# Power.net
KiCad netlist of a schematic drawn in Altium Designer
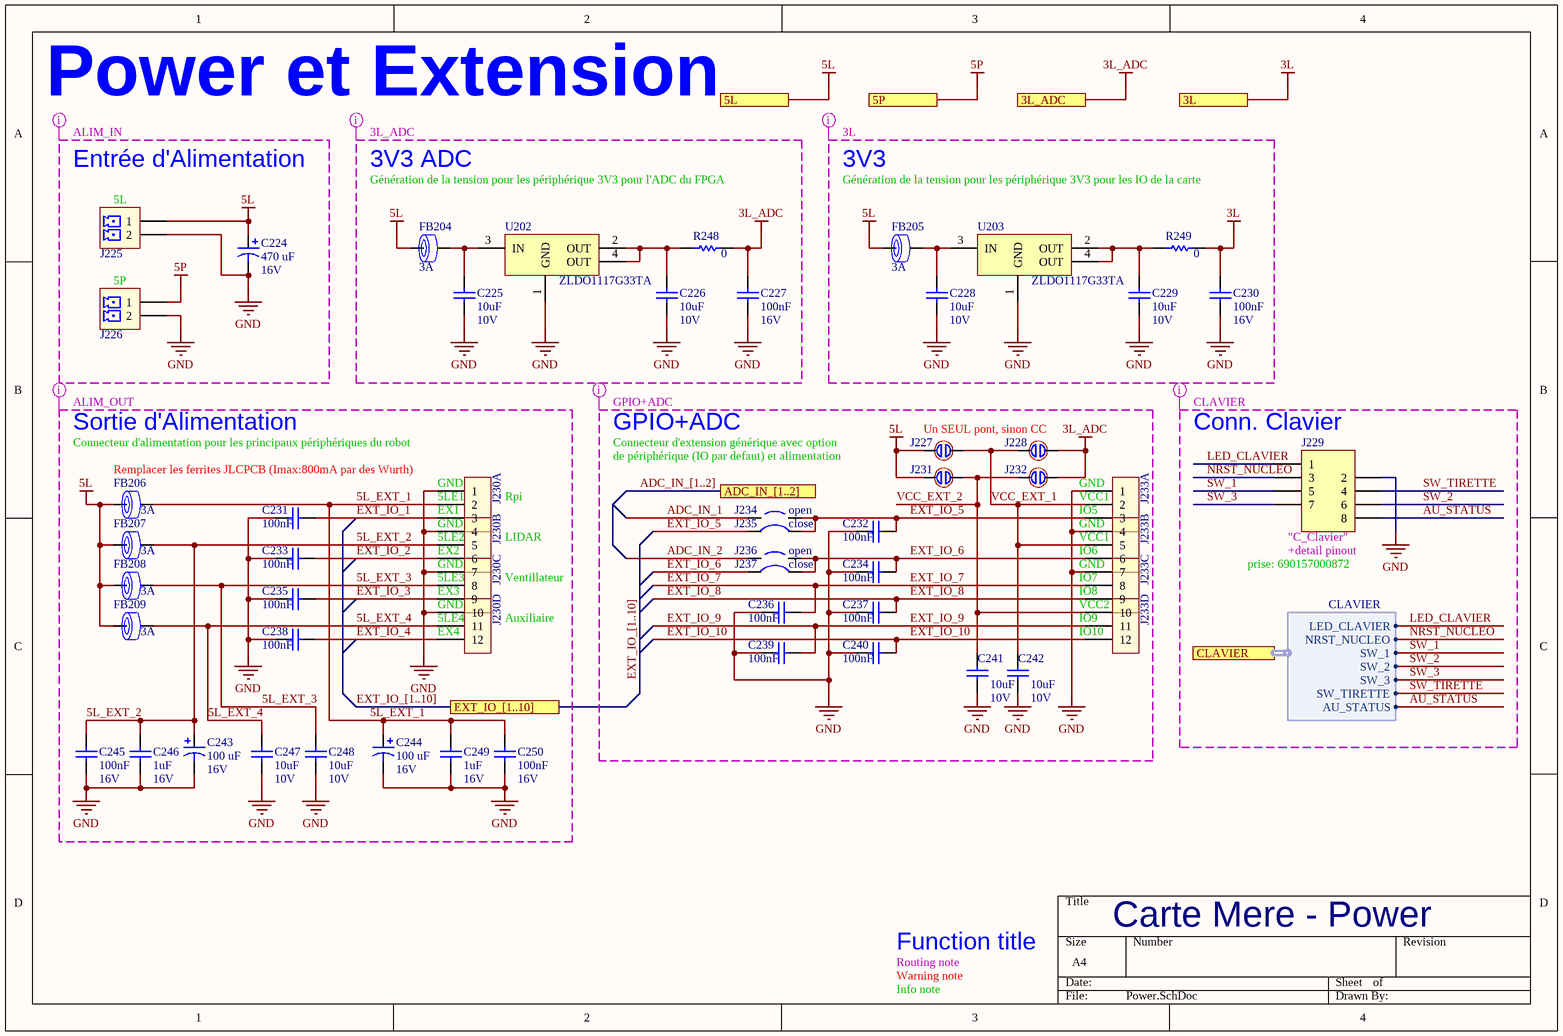
[diagram p0: Power.SchDoc]

(export (version "E")
  (design (tool "Eeschema 10.0.6"))
  (components
    (comp (ref "C224")
      (value "470 uF")
      (footprint "WCAP-ATG8_8x11.5x3.5x0.5")
      (description "CAP Alu 470 UF 20% 16 V")
      (fields
        (field (name "MANUFACTURER") "Wurth Elektronik")
        (field (name "MANUFACTURER PART NUMBER") "860010374012")
        (field (name "RATEDVOLTAGE") "16V")
      )
      (libsource (lib "Condensateur") (part "WCAP-ATG8, 860010374012"))
    )
    (comp (ref "C225")
      (value "10uF")
      (footprint "WCAP-CSGP_0805, 2x1.25x1.25")
      (description "CAP CER 10uF 10V X7R 0805")
      (fields
        (field (name "MANUFACTURER") "Wurth Elektronik")
        (field (name "MANUFACTURER PART NUMBER") "885012207026")
        (field (name "RATEDVOLTAGE") "10V")
      )
      (libsource (lib "Condensateur") (part "WCAP-CSGP, 885012207026"))
    )
    (comp (ref "C226")
      (value "10uF")
      (footprint "WCAP-CSGP_0805, 2x1.25x1.25")
      (description "CAP CER 10uF 10V X7R 0805")
      (fields
        (field (name "MANUFACTURER") "Wurth Elektronik")
        (field (name "MANUFACTURER PART NUMBER") "885012207026")
        (field (name "RATEDVOLTAGE") "10V")
      )
      (libsource (lib "Condensateur") (part "WCAP-CSGP, 885012207026"))
    )
    (comp (ref "C227")
      (value "100nF")
      (footprint "WCAP-CSGP_0402, 1x0.5x0.5")
      (description "CAP CER 100nF 16V X7R 0402")
      (fields
        (field (name "MANUFACTURER") "Wurth Elektronik")
        (field (name "MANUFACTURER PART NUMBER") "885012205037")
        (field (name "RATEDVOLTAGE") "16V")
      )
      (libsource (lib "Condensateur") (part "WCAP-CSGP, 885012205037"))
    )
    (comp (ref "C228")
      (value "10uF")
      (footprint "WCAP-CSGP_0805, 2x1.25x1.25")
      (description "CAP CER 10uF 10V X7R 0805")
      (fields
        (field (name "MANUFACTURER") "Wurth Elektronik")
        (field (name "MANUFACTURER PART NUMBER") "885012207026")
        (field (name "RATEDVOLTAGE") "10V")
      )
      (libsource (lib "Condensateur") (part "WCAP-CSGP, 885012207026"))
    )
    (comp (ref "C229")
      (value "10uF")
      (footprint "WCAP-CSGP_0805, 2x1.25x1.25")
      (description "CAP CER 10uF 10V X7R 0805")
      (fields
        (field (name "MANUFACTURER") "Wurth Elektronik")
        (field (name "MANUFACTURER PART NUMBER") "885012207026")
        (field (name "RATEDVOLTAGE") "10V")
      )
      (libsource (lib "Condensateur") (part "WCAP-CSGP, 885012207026"))
    )
    (comp (ref "C230")
      (value "100nF")
      (footprint "WCAP-CSGP_0402, 1x0.5x0.5")
      (description "CAP CER 100nF 16V X7R 0402")
      (fields
        (field (name "MANUFACTURER") "Wurth Elektronik")
        (field (name "MANUFACTURER PART NUMBER") "885012205037")
        (field (name "RATEDVOLTAGE") "16V")
      )
      (libsource (lib "Condensateur") (part "WCAP-CSGP, 885012205037"))
    )
    (comp (ref "C231")
      (value "100nF")
      (footprint "WCAP-CSGP_0402, 1x0.5x0.5")
      (description "CAP CER 100nF 16V X7R 0402")
      (fields
        (field (name "MANUFACTURER") "Wurth Elektronik")
        (field (name "MANUFACTURER PART NUMBER") "885012205037")
      )
      (libsource (lib "Condensateur") (part "WCAP-CSGP, 885012205037"))
    )
    (comp (ref "C232")
      (value "100nF")
      (footprint "WCAP-CSGP_0402, 1x0.5x0.5")
      (description "CAP CER 100nF 16V X7R 0402")
      (fields
        (field (name "MANUFACTURER") "Wurth Elektronik")
        (field (name "MANUFACTURER PART NUMBER") "885012205037")
      )
      (libsource (lib "Condensateur") (part "WCAP-CSGP, 885012205037"))
    )
    (comp (ref "C233")
      (value "100nF")
      (footprint "WCAP-CSGP_0402, 1x0.5x0.5")
      (description "CAP CER 100nF 16V X7R 0402")
      (fields
        (field (name "MANUFACTURER") "Wurth Elektronik")
        (field (name "MANUFACTURER PART NUMBER") "885012205037")
      )
      (libsource (lib "Condensateur") (part "WCAP-CSGP, 885012205037"))
    )
    (comp (ref "C234")
      (value "100nF")
      (footprint "WCAP-CSGP_0402, 1x0.5x0.5")
      (description "CAP CER 100nF 16V X7R 0402")
      (fields
        (field (name "MANUFACTURER") "Wurth Elektronik")
        (field (name "MANUFACTURER PART NUMBER") "885012205037")
      )
      (libsource (lib "Condensateur") (part "WCAP-CSGP, 885012205037"))
    )
    (comp (ref "C235")
      (value "100nF")
      (footprint "WCAP-CSGP_0402, 1x0.5x0.5")
      (description "CAP CER 100nF 16V X7R 0402")
      (fields
        (field (name "MANUFACTURER") "Wurth Elektronik")
        (field (name "MANUFACTURER PART NUMBER") "885012205037")
      )
      (libsource (lib "Condensateur") (part "WCAP-CSGP, 885012205037"))
    )
    (comp (ref "C236")
      (value "100nF")
      (footprint "WCAP-CSGP_0402, 1x0.5x0.5")
      (description "CAP CER 100nF 16V X7R 0402")
      (fields
        (field (name "MANUFACTURER") "Wurth Elektronik")
        (field (name "MANUFACTURER PART NUMBER") "885012205037")
      )
      (libsource (lib "Condensateur") (part "WCAP-CSGP, 885012205037"))
    )
    (comp (ref "C237")
      (value "100nF")
      (footprint "WCAP-CSGP_0402, 1x0.5x0.5")
      (description "CAP CER 100nF 16V X7R 0402")
      (fields
        (field (name "MANUFACTURER") "Wurth Elektronik")
        (field (name "MANUFACTURER PART NUMBER") "885012205037")
      )
      (libsource (lib "Condensateur") (part "WCAP-CSGP, 885012205037"))
    )
    (comp (ref "C238")
      (value "100nF")
      (footprint "WCAP-CSGP_0402, 1x0.5x0.5")
      (description "CAP CER 100nF 16V X7R 0402")
      (fields
        (field (name "MANUFACTURER") "Wurth Elektronik")
        (field (name "MANUFACTURER PART NUMBER") "885012205037")
      )
      (libsource (lib "Condensateur") (part "WCAP-CSGP, 885012205037"))
    )
    (comp (ref "C239")
      (value "100nF")
      (footprint "WCAP-CSGP_0402, 1x0.5x0.5")
      (description "CAP CER 100nF 16V X7R 0402")
      (fields
        (field (name "MANUFACTURER") "Wurth Elektronik")
        (field (name "MANUFACTURER PART NUMBER") "885012205037")
      )
      (libsource (lib "Condensateur") (part "WCAP-CSGP, 885012205037"))
    )
    (comp (ref "C240")
      (value "100nF")
      (footprint "WCAP-CSGP_0402, 1x0.5x0.5")
      (description "CAP CER 100nF 16V X7R 0402")
      (fields
        (field (name "MANUFACTURER") "Wurth Elektronik")
        (field (name "MANUFACTURER PART NUMBER") "885012205037")
      )
      (libsource (lib "Condensateur") (part "WCAP-CSGP, 885012205037"))
    )
    (comp (ref "C241")
      (value "10uF")
      (footprint "WCAP-CSGP_0805, 2x1.25x1.25")
      (description "CAP CER 10uF 10V X7R 0805")
      (fields
        (field (name "MANUFACTURER") "Wurth Elektronik")
        (field (name "MANUFACTURER PART NUMBER") "885012207026")
        (field (name "RATEDVOLTAGE") "10V")
      )
      (libsource (lib "Condensateur") (part "WCAP-CSGP, 885012207026"))
    )
    (comp (ref "C242")
      (value "10uF")
      (footprint "WCAP-CSGP_0805, 2x1.25x1.25")
      (description "CAP CER 10uF 10V X7R 0805")
      (fields
        (field (name "MANUFACTURER") "Wurth Elektronik")
        (field (name "MANUFACTURER PART NUMBER") "885012207026")
        (field (name "RATEDVOLTAGE") "10V")
      )
      (libsource (lib "Condensateur") (part "WCAP-CSGP, 885012207026"))
    )
    (comp (ref "C243")
      (value "100 uF")
      (footprint "WCAP-ATG8_5x11x2x0.5")
      (description "CAP Alu 100 UF 20% 16 V")
      (fields
        (field (name "MANUFACTURER") "Wurth Elektronik")
        (field (name "MANUFACTURER PART NUMBER") "860010372006")
        (field (name "RATEDVOLTAGE") "16V")
      )
      (libsource (lib "") (part "WCAP-ATG8, 860010372006_1"))
    )
    (comp (ref "C244")
      (value "100 uF")
      (footprint "WCAP-ATG8_5x11x2x0.5")
      (description "CAP Alu 100 UF 20% 16 V")
      (fields
        (field (name "MANUFACTURER") "Wurth Elektronik")
        (field (name "MANUFACTURER PART NUMBER") "860010372006")
        (field (name "RATEDVOLTAGE") "16V")
      )
      (libsource (lib "Condensateur") (part "WCAP-ATG8, 860010372006"))
    )
    (comp (ref "C245")
      (value "100nF")
      (footprint "WCAP-CSGP_0402, 1x0.5x0.5")
      (description "CAP CER 100nF 16V X7R 0402")
      (fields
        (field (name "MANUFACTURER") "Wurth Elektronik")
        (field (name "MANUFACTURER PART NUMBER") "885012205037")
        (field (name "RATEDVOLTAGE") "16V")
      )
      (libsource (lib "Condensateur") (part "WCAP-CSGP, 885012205037"))
    )
    (comp (ref "C246")
      (value "1uF")
      (footprint "WCAP-CSGP_0603, 1.6x0.8x0.8")
      (description "CAP CER 1UF 16V X5R 0603")
      (fields
        (field (name "MANUFACTURER") "Wurth Elektronik")
        (field (name "MANUFACTURER PART NUMBER") "885012106017")
        (field (name "RATEDVOLTAGE") "16V")
      )
      (libsource (lib "Condensateur") (part "WCAP-CSGP, 885012106017"))
    )
    (comp (ref "C247")
      (value "10uF")
      (footprint "WCAP-CSGP_0805, 2x1.25x1.25")
      (description "CAP CER 10uF 10V X7R 0805")
      (fields
        (field (name "MANUFACTURER") "Wurth Elektronik")
        (field (name "MANUFACTURER PART NUMBER") "885012207026")
        (field (name "RATEDVOLTAGE") "10V")
      )
      (libsource (lib "Condensateur") (part "WCAP-CSGP, 885012207026"))
    )
    (comp (ref "C248")
      (value "10uF")
      (footprint "WCAP-CSGP_0805, 2x1.25x1.25")
      (description "CAP CER 10uF 10V X7R 0805")
      (fields
        (field (name "MANUFACTURER") "Wurth Elektronik")
        (field (name "MANUFACTURER PART NUMBER") "885012207026")
        (field (name "RATEDVOLTAGE") "10V")
      )
      (libsource (lib "Condensateur") (part "WCAP-CSGP, 885012207026"))
    )
    (comp (ref "C249")
      (value "1uF")
      (footprint "WCAP-CSGP_0603, 1.6x0.8x0.8")
      (description "CAP CER 1UF 16V X5R 0603")
      (fields
        (field (name "MANUFACTURER") "Wurth Elektronik")
        (field (name "MANUFACTURER PART NUMBER") "885012106017")
        (field (name "RATEDVOLTAGE") "16V")
      )
      (libsource (lib "Condensateur") (part "WCAP-CSGP, 885012106017"))
    )
    (comp (ref "C250")
      (value "100nF")
      (footprint "WCAP-CSGP_0402, 1x0.5x0.5")
      (description "CAP CER 100nF 16V X7R 0402")
      (fields
        (field (name "MANUFACTURER") "Wurth Elektronik")
        (field (name "MANUFACTURER PART NUMBER") "885012205037")
        (field (name "RATEDVOLTAGE") "16V")
      )
      (libsource (lib "Condensateur") (part "WCAP-CSGP, 885012205037"))
    )
    (comp (ref "FB204")
      (value "742792023")
      (footprint "WE-CBF_0805_High Current")
      (description "Ferrite Bead 120ohm 0805 3A")
      (fields (field (name "MANUFACTURER") "Wurth Elektronik") (field (name "RATEDCURRENT") "3A"))
      (libsource (lib "Inductance") (part "WE-CBF, 742792023"))
    )
    (comp (ref "FB205")
      (value "742792023")
      (footprint "WE-CBF_0805_High Current")
      (description "Ferrite Bead 120ohm 0805 3A")
      (fields (field (name "MANUFACTURER") "Wurth Elektronik") (field (name "RATEDCURRENT") "3A"))
      (libsource (lib "Inductance") (part "WE-CBF, 742792023"))
    )
    (comp (ref "FB206")
      (value "742792023")
      (footprint "WE-CBF_0805_High Current")
      (description "Ferrite Bead 120ohm 0805 3A")
      (fields (field (name "MANUFACTURER") "Wurth Elektronik") (field (name "RATEDCURRENT") "3A"))
      (libsource (lib "Inductance") (part "WE-CBF, 742792023"))
    )
    (comp (ref "FB207")
      (value "742792023")
      (footprint "WE-CBF_0805_High Current")
      (description "Ferrite Bead 120ohm 0805 3A")
      (fields (field (name "MANUFACTURER") "Wurth Elektronik") (field (name "RATEDCURRENT") "3A"))
      (libsource (lib "Inductance") (part "WE-CBF, 742792023"))
    )
    (comp (ref "FB208")
      (value "742792023")
      (footprint "WE-CBF_0805_High Current")
      (description "Ferrite Bead 120ohm 0805 3A")
      (fields (field (name "MANUFACTURER") "Wurth Elektronik") (field (name "RATEDCURRENT") "3A"))
      (libsource (lib "Inductance") (part "WE-CBF, 742792023"))
    )
    (comp (ref "FB209")
      (value "742792023")
      (footprint "WE-CBF_0805_High Current")
      (description "Ferrite Bead 120ohm 0805 3A")
      (fields (field (name "MANUFACTURER") "Wurth Elektronik") (field (name "RATEDCURRENT") "3A"))
      (libsource (lib "Inductance") (part "WE-CBF, 742792023"))
    )
    (comp (ref "J225")
      (value "691322110002")
      (footprint "691322110002")
      (description "WR-TBL 2p Series 3221 - 3.50 mm Horizontal PCB Header")
      (fields (field (name "MANUFACTURER") "Wurth Electronics Inc."))
      (libsource (lib "Connecteurs") (part "691322110002"))
    )
    (comp (ref "J226")
      (value "691322110002")
      (footprint "691322110002")
      (description "WR-TBL 2p Series 3221 - 3.50 mm Horizontal PCB Header")
      (fields (field (name "MANUFACTURER") "Wurth Electronics Inc."))
      (libsource (lib "Connecteurs") (part "691322110002"))
    )
    (comp (ref "J227")
      (value "open")
      (footprint "CAVALIER")
      (description "Cavalier soudure \"ouvert\", pastille fendue 1.2mm")
      (libsource (lib "Divers") (part "CAVALIER_DOT"))
    )
    (comp (ref "J228")
      (value "open")
      (footprint "CAVALIER")
      (description "Cavalier soudure \"ouvert\", pastille fendue 1.2mm")
      (libsource (lib "Divers") (part "CAVALIER_DOT"))
    )
    (comp (ref "J229")
      (value "690367280876")
      (footprint "690367280876")
      (description "WR-MM 8p Female SMT Connector with Polarization")
      (fields (field (name "MANUFACTURER") "Wurth Electronics Inc."))
      (libsource (lib "Connecteurs") (part "690367280876"))
    )
    (comp (ref "J230")
      (value "TSW-104-08-F-T-RA")
      (footprint "TSW-104-08-F-T-RA")
      (description "CONN HEADER R/A 3L x 4POS 2.54MM")
      (fields (field (name "MANUFACTURER") "SAMTEC"))
      (libsource (lib "Connecteurs") (part "TSW-104-08-F-T-RA"))
    )
    (comp (ref "J231")
      (value "open")
      (footprint "CAVALIER")
      (description "Cavalier soudure \"ouvert\", pastille fendue 1.2mm")
      (libsource (lib "Divers") (part "CAVALIER_DOT"))
    )
    (comp (ref "J232")
      (value "open")
      (footprint "CAVALIER")
      (description "Cavalier soudure \"ouvert\", pastille fendue 1.2mm")
      (libsource (lib "Divers") (part "CAVALIER_DOT"))
    )
    (comp (ref "J233")
      (value "TSW-104-08-F-T-RA")
      (footprint "TSW-104-08-F-T-RA")
      (description "CONN HEADER R/A 3L x 4POS 2.54MM")
      (fields (field (name "MANUFACTURER") "SAMTEC"))
      (libsource (lib "Connecteurs") (part "TSW-104-08-F-T-RA"))
    )
    (comp (ref "J234")
      (value "open")
      (footprint "CAVALIER_0603_O")
      (description "Cavalier soudure \"ouvert\" + empreinte dipole 0603")
      (libsource (lib "Divers") (part "CAVALIER_0603_O"))
    )
    (comp (ref "J235")
      (value "close")
      (footprint "CAVALIER_0603_C")
      (description "Cavalier soudure \"fermé\" + empreinte dipole 0603")
      (libsource (lib "Divers") (part "CAVALIER_0603_C"))
    )
    (comp (ref "J236")
      (value "open")
      (footprint "CAVALIER_0603_O")
      (description "Cavalier soudure \"ouvert\" + empreinte dipole 0603")
      (libsource (lib "Divers") (part "CAVALIER_0603_O"))
    )
    (comp (ref "J237")
      (value "close")
      (footprint "CAVALIER_0603_C")
      (description "Cavalier soudure \"fermé\" + empreinte dipole 0603")
      (libsource (lib "Divers") (part "CAVALIER_0603_C"))
    )
    (comp (ref "R248")
      (value "0")
      (footprint "RESC1608X06N")
      (description "RES SMD 0 OHM 1% 1/10W 0603")
      (fields
        (field (name "MANUFACTURER") "Yageo")
        (field (name "MANUFACTURER PART NUMBER") "RC0603FR-070RL")
      )
      (libsource (lib "Resistance") (part "RC0603FR-070RL"))
    )
    (comp (ref "R249")
      (value "0")
      (footprint "RESC1608X06N")
      (description "RES SMD 0 OHM 1% 1/10W 0603")
      (fields
        (field (name "MANUFACTURER") "Yageo")
        (field (name "MANUFACTURER PART NUMBER") "RC0603FR-070RL")
      )
      (libsource (lib "Resistance") (part "RC0603FR-070RL"))
    )
    (comp (ref "U202")
      (value "ZLDO1117G33TA")
      (footprint "SOT223")
      (description "LDO 3.3V 1A SOT223-3")
      (fields (field (name "MANUFACTURER") "Diodes Inc."))
      (libsource (lib "Alimentation") (part "ZLDO1117G33TA"))
    )
    (comp (ref "U203")
      (value "ZLDO1117G33TA")
      (footprint "SOT223")
      (description "LDO 3.3V 1A SOT223-3")
      (fields (field (name "MANUFACTURER") "Diodes Inc."))
      (libsource (lib "Alimentation") (part "ZLDO1117G33TA"))
    )
  )
  (nets
    (net (code "2") (name "/5L_EXT_1") (class "Default")
      (node (ref "C244") (pin "1") (pinfunction "1_1") (pintype "passive"))
      (node (ref "C249") (pin "1") (pinfunction "1_1") (pintype "passive"))
      (node (ref "C250") (pin "1") (pinfunction "1_1") (pintype "passive"))
      (node (ref "FB206") (pin "2") (pinfunction "2_2") (pintype "passive"))
      (node (ref "J230") (pin "2") (pinfunction "2_2") (pintype "passive"))
    )
    (net (code "3") (name "/5L_EXT_2") (class "Default")
      (node (ref "C243") (pin "1") (pinfunction "1_1") (pintype "passive"))
      (node (ref "C245") (pin "1") (pinfunction "1_1") (pintype "passive"))
      (node (ref "C246") (pin "1") (pinfunction "1_1") (pintype "passive"))
      (node (ref "FB207") (pin "2") (pinfunction "2_2") (pintype "passive"))
      (node (ref "J230") (pin "5") (pinfunction "5_5") (pintype "passive"))
    )
    (net (code "4") (name "/5L_EXT_3") (class "Default")
      (node (ref "C248") (pin "1") (pinfunction "1_1") (pintype "passive"))
      (node (ref "FB208") (pin "2") (pinfunction "2_2") (pintype "passive"))
      (node (ref "J230") (pin "8") (pinfunction "8_8") (pintype "passive"))
    )
    (net (code "5") (name "/5L_EXT_4") (class "Default")
      (node (ref "C247") (pin "1") (pinfunction "1_1") (pintype "passive"))
      (node (ref "FB209") (pin "2") (pinfunction "2_2") (pintype "passive"))
      (node (ref "J230") (pin "11") (pinfunction "11_11") (pintype "passive"))
    )
    (net (code "6") (name "/ADC_IN_1") (class "Default")
      (node (ref "J234") (pin "1") (pinfunction "1_1") (pintype "passive"))
    )
    (net (code "7") (name "/ADC_IN_2") (class "Default")
      (node (ref "J236") (pin "1") (pinfunction "1_1") (pintype "passive"))
    )
    (net (code "9") (name "/AU_STATUS") (class "Default")
      (node (ref "J229") (pin "8") (pinfunction "8_8") (pintype "passive"))
    )
    (net (code "10") (name "/EXT_IO_1") (class "Default")
      (node (ref "C231") (pin "1") (pinfunction "1_1") (pintype "passive"))
      (node (ref "J230") (pin "3") (pinfunction "3_3") (pintype "passive"))
    )
    (net (code "11") (name "/EXT_IO_2") (class "Default")
      (node (ref "C233") (pin "1") (pinfunction "1_1") (pintype "passive"))
      (node (ref "J230") (pin "6") (pinfunction "6_6") (pintype "passive"))
    )
    (net (code "12") (name "/EXT_IO_3") (class "Default")
      (node (ref "C235") (pin "1") (pinfunction "1_1") (pintype "passive"))
      (node (ref "J230") (pin "9") (pinfunction "9_9") (pintype "passive"))
    )
    (net (code "13") (name "/EXT_IO_4") (class "Default")
      (node (ref "C238") (pin "1") (pinfunction "1_1") (pintype "passive"))
      (node (ref "J230") (pin "12") (pinfunction "12_12") (pintype "passive"))
    )
    (net (code "14") (name "/EXT_IO_5") (class "Default")
      (node (ref "C232") (pin "1") (pinfunction "1_1") (pintype "passive"))
      (node (ref "J233") (pin "3") (pinfunction "3_3") (pintype "passive"))
      (node (ref "J234") (pin "2") (pinfunction "2_2") (pintype "passive"))
      (node (ref "J235") (pin "1") (pinfunction "1_1") (pintype "passive"))
      (node (ref "J235") (pin "2") (pinfunction "2_2") (pintype "passive"))
    )
    (net (code "15") (name "/EXT_IO_6") (class "Default")
      (node (ref "C234") (pin "1") (pinfunction "1_1") (pintype "passive"))
      (node (ref "J233") (pin "6") (pinfunction "6_6") (pintype "passive"))
      (node (ref "J236") (pin "2") (pinfunction "2_2") (pintype "passive"))
      (node (ref "J237") (pin "1") (pinfunction "1_1") (pintype "passive"))
      (node (ref "J237") (pin "2") (pinfunction "2_2") (pintype "passive"))
    )
    (net (code "16") (name "/EXT_IO_7") (class "Default")
      (node (ref "C236") (pin "1") (pinfunction "1_1") (pintype "passive"))
      (node (ref "J233") (pin "8") (pinfunction "8_8") (pintype "passive"))
    )
    (net (code "17") (name "/EXT_IO_8") (class "Default")
      (node (ref "C237") (pin "1") (pinfunction "1_1") (pintype "passive"))
      (node (ref "J233") (pin "9") (pinfunction "9_9") (pintype "passive"))
    )
    (net (code "18") (name "/EXT_IO_9") (class "Default")
      (node (ref "C239") (pin "1") (pinfunction "1_1") (pintype "passive"))
      (node (ref "J233") (pin "11") (pinfunction "11_11") (pintype "passive"))
    )
    (net (code "19") (name "/EXT_IO_10") (class "Default")
      (node (ref "C240") (pin "1") (pinfunction "1_1") (pintype "passive"))
      (node (ref "J233") (pin "12") (pinfunction "12_12") (pintype "passive"))
    )
    (net (code "21") (name "/LED_CLAVIER") (class "Default")
      (node (ref "J229") (pin "1") (pinfunction "1_1") (pintype "passive"))
    )
    (net (code "22") (name "/NRST_NUCLEO") (class "Default")
      (node (ref "J229") (pin "3") (pinfunction "3_3") (pintype "passive"))
    )
    (net (code "23") (name "/SW_1") (class "Default")
      (node (ref "J229") (pin "5") (pinfunction "5_5") (pintype "passive"))
    )
    (net (code "24") (name "/SW_2") (class "Default")
      (node (ref "J229") (pin "6") (pinfunction "6_6") (pintype "passive"))
    )
    (net (code "25") (name "/SW_3") (class "Default")
      (node (ref "J229") (pin "7") (pinfunction "7_7") (pintype "passive"))
    )
    (net (code "26") (name "/SW_TIRETTE") (class "Default")
      (node (ref "J229") (pin "4") (pinfunction "4_4") (pintype "passive"))
    )
    (net (code "27") (name "/VCC_EXT_1") (class "Default")
      (node (ref "C242") (pin "1") (pinfunction "1_1") (pintype "passive"))
      (node (ref "J227") (pin "1") (pinfunction "1_1") (pintype "passive"))
      (node (ref "J228") (pin "2") (pinfunction "2_2") (pintype "passive"))
      (node (ref "J233") (pin "2") (pinfunction "2_2") (pintype "passive"))
      (node (ref "J233") (pin "5") (pinfunction "5_5") (pintype "passive"))
    )
    (net (code "28") (name "/VCC_EXT_2") (class "Default")
      (node (ref "C241") (pin "1") (pinfunction "1_1") (pintype "passive"))
      (node (ref "J231") (pin "1") (pinfunction "1_1") (pintype "passive"))
      (node (ref "J232") (pin "2") (pinfunction "2_2") (pintype "passive"))
      (node (ref "J233") (pin "10") (pinfunction "10_10") (pintype "passive"))
    )
    (net (code "30") (name "3L") (class "Default")
      (node (ref "C230") (pin "1") (pinfunction "1_1") (pintype "passive"))
      (node (ref "R249") (pin "2") (pinfunction "2_2") (pintype "passive"))
    )
    (net (code "31") (name "3L_ADC") (class "Default")
      (node (ref "C227") (pin "1") (pinfunction "1_1") (pintype "passive"))
      (node (ref "J228") (pin "1") (pinfunction "1_1") (pintype "passive"))
      (node (ref "J232") (pin "1") (pinfunction "1_1") (pintype "passive"))
      (node (ref "R248") (pin "2") (pinfunction "2_2") (pintype "passive"))
    )
    (net (code "32") (name "5L") (class "Default")
      (node (ref "C224") (pin "1") (pinfunction "1_1") (pintype "passive"))
      (node (ref "FB204") (pin "1") (pinfunction "1_1") (pintype "passive"))
      (node (ref "FB205") (pin "1") (pinfunction "1_1") (pintype "passive"))
      (node (ref "FB206") (pin "1") (pinfunction "1_1") (pintype "passive"))
      (node (ref "FB207") (pin "1") (pinfunction "1_1") (pintype "passive"))
      (node (ref "FB208") (pin "1") (pinfunction "1_1") (pintype "passive"))
      (node (ref "FB209") (pin "1") (pinfunction "1_1") (pintype "passive"))
      (node (ref "J225") (pin "1") (pinfunction "1_1") (pintype "passive"))
      (node (ref "J227") (pin "2") (pinfunction "2_2") (pintype "passive"))
      (node (ref "J231") (pin "2") (pinfunction "2_2") (pintype "passive"))
    )
    (net (code "33") (name "5P") (class "Default")
      (node (ref "J226") (pin "1") (pinfunction "1_1") (pintype "passive"))
    )
    (net (code "34") (name "GND") (class "Default")
      (node (ref "C224") (pin "2") (pinfunction "2_2") (pintype "passive"))
      (node (ref "C225") (pin "2") (pinfunction "2_2") (pintype "passive"))
      (node (ref "C226") (pin "2") (pinfunction "2_2") (pintype "passive"))
      (node (ref "C227") (pin "2") (pinfunction "2_2") (pintype "passive"))
      (node (ref "C228") (pin "2") (pinfunction "2_2") (pintype "passive"))
      (node (ref "C229") (pin "2") (pinfunction "2_2") (pintype "passive"))
      (node (ref "C230") (pin "2") (pinfunction "2_2") (pintype "passive"))
      (node (ref "C231") (pin "2") (pinfunction "2_2") (pintype "passive"))
      (node (ref "C232") (pin "2") (pinfunction "2_2") (pintype "passive"))
      (node (ref "C233") (pin "2") (pinfunction "2_2") (pintype "passive"))
      (node (ref "C234") (pin "2") (pinfunction "2_2") (pintype "passive"))
      (node (ref "C235") (pin "2") (pinfunction "2_2") (pintype "passive"))
      (node (ref "C236") (pin "2") (pinfunction "2_2") (pintype "passive"))
      (node (ref "C237") (pin "2") (pinfunction "2_2") (pintype "passive"))
      (node (ref "C238") (pin "2") (pinfunction "2_2") (pintype "passive"))
      (node (ref "C239") (pin "2") (pinfunction "2_2") (pintype "passive"))
      (node (ref "C240") (pin "2") (pinfunction "2_2") (pintype "passive"))
      (node (ref "C241") (pin "2") (pinfunction "2_2") (pintype "passive"))
      (node (ref "C242") (pin "2") (pinfunction "2_2") (pintype "passive"))
      (node (ref "C243") (pin "2") (pinfunction "2_2") (pintype "passive"))
      (node (ref "C244") (pin "2") (pinfunction "2_2") (pintype "passive"))
      (node (ref "C245") (pin "2") (pinfunction "2_2") (pintype "passive"))
      (node (ref "C246") (pin "2") (pinfunction "2_2") (pintype "passive"))
      (node (ref "C247") (pin "2") (pinfunction "2_2") (pintype "passive"))
      (node (ref "C248") (pin "2") (pinfunction "2_2") (pintype "passive"))
      (node (ref "C249") (pin "2") (pinfunction "2_2") (pintype "passive"))
      (node (ref "C250") (pin "2") (pinfunction "2_2") (pintype "passive"))
      (node (ref "J225") (pin "2") (pinfunction "2_2") (pintype "passive"))
      (node (ref "J226") (pin "2") (pinfunction "2_2") (pintype "passive"))
      (node (ref "J229") (pin "2") (pinfunction "2_2") (pintype "passive"))
      (node (ref "J230") (pin "1") (pinfunction "1_1") (pintype "passive"))
      (node (ref "J230") (pin "10") (pinfunction "10_10") (pintype "passive"))
      (node (ref "J230") (pin "4") (pinfunction "4_4") (pintype "passive"))
      (node (ref "J230") (pin "7") (pinfunction "7_7") (pintype "passive"))
      (node (ref "J233") (pin "1") (pinfunction "1_1") (pintype "passive"))
      (node (ref "J233") (pin "4") (pinfunction "4_4") (pintype "passive"))
      (node (ref "J233") (pin "7") (pinfunction "7_7") (pintype "passive"))
      (node (ref "U202") (pin "1") (pinfunction "GND_1") (pintype "power_in"))
      (node (ref "U203") (pin "1") (pinfunction "GND_1") (pintype "power_in"))
    )
    (net (code "35") (name "Net-(C226-Pad1)") (class "Default")
      (node (ref "C226") (pin "1") (pinfunction "1_1") (pintype "passive"))
      (node (ref "R248") (pin "1") (pinfunction "1_1") (pintype "passive"))
      (node (ref "U202") (pin "2") (pinfunction "OUT_2") (pintype "power_in"))
      (node (ref "U202") (pin "4") (pinfunction "OUT_4") (pintype "power_in"))
    )
    (net (code "36") (name "Net-(C229-Pad1)") (class "Default")
      (node (ref "C229") (pin "1") (pinfunction "1_1") (pintype "passive"))
      (node (ref "R249") (pin "1") (pinfunction "1_1") (pintype "passive"))
      (node (ref "U203") (pin "2") (pinfunction "OUT_2") (pintype "power_in"))
      (node (ref "U203") (pin "4") (pinfunction "OUT_4") (pintype "power_in"))
    )
    (net (code "37") (name "Net-(U202-IN)") (class "Default")
      (node (ref "C225") (pin "1") (pinfunction "1_1") (pintype "passive"))
      (node (ref "FB204") (pin "2") (pinfunction "2_2") (pintype "passive"))
      (node (ref "U202") (pin "3") (pinfunction "IN_3") (pintype "power_in"))
    )
    (net (code "38") (name "Net-(U203-IN)") (class "Default")
      (node (ref "C228") (pin "1") (pinfunction "1_1") (pintype "passive"))
      (node (ref "FB205") (pin "2") (pinfunction "2_2") (pintype "passive"))
      (node (ref "U203") (pin "3") (pinfunction "IN_3") (pintype "power_in"))
    )
  )
)
